# Main.net
KiCad netlist of a schematic drawn in EAGLE
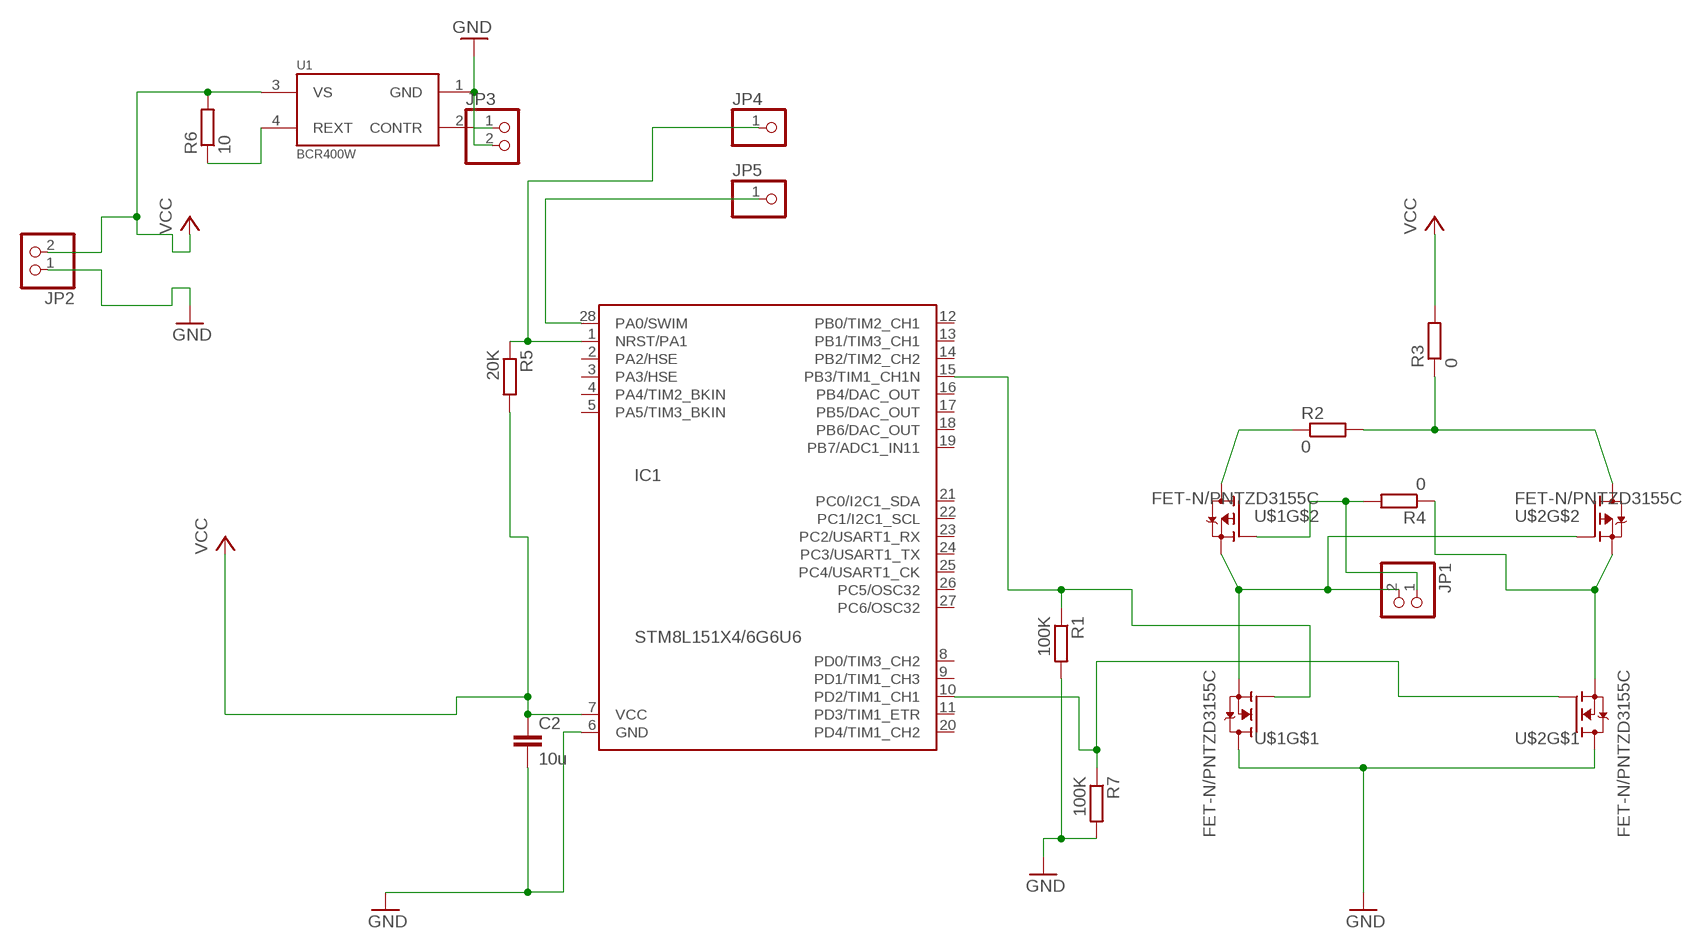
[diagram p0: schematic, sheet 1]

(export (version "E")
  (design (tool "Eeschema 10.0.6"))
  (components
    (comp (ref "C2")
      (value "10u")
      (footprint "eagle-import:C0805")
      (libsource (lib "eagle-import") (part "C-EUC0805"))
    )
    (comp (ref "IC1")
      (value "STM8L151X4/6G6U6")
      (footprint "eagle-import:QFN28")
      (libsource (lib "eagle-import") (part "STM8L151X4/6G6U6"))
    )
    (comp (ref "JP1")
      (value "PINHD-1X2")
      (footprint "eagle-import:1X02")
      (libsource (lib "eagle-import") (part "PINHD-1X2"))
    )
    (comp (ref "JP2")
      (value "PINHD-1X2")
      (footprint "eagle-import:1X02")
      (libsource (lib "eagle-import") (part "PINHD-1X2"))
    )
    (comp (ref "JP3")
      (value "PINHD-1X2")
      (footprint "eagle-import:1X02")
      (libsource (lib "eagle-import") (part "PINHD-1X2"))
    )
    (comp (ref "JP4")
      (value "PINHD-1X1")
      (footprint "eagle-import:1X01")
      (libsource (lib "eagle-import") (part "PINHD-1X1"))
    )
    (comp (ref "JP5")
      (value "PINHD-1X1")
      (footprint "eagle-import:1X01")
      (libsource (lib "eagle-import") (part "PINHD-1X1"))
    )
    (comp (ref "R1")
      (value "100K")
      (footprint "eagle-import:R0805")
      (libsource (lib "eagle-import") (part "R_0805"))
    )
    (comp (ref "R2")
      (value "0")
      (footprint "eagle-import:R0805")
      (libsource (lib "eagle-import") (part "R_0805"))
    )
    (comp (ref "R3")
      (value "0")
      (footprint "eagle-import:R0805")
      (libsource (lib "eagle-import") (part "R_0805"))
    )
    (comp (ref "R4")
      (value "0")
      (footprint "eagle-import:R0805")
      (libsource (lib "eagle-import") (part "R_0805"))
    )
    (comp (ref "R5")
      (value "20K")
      (footprint "eagle-import:R0805")
      (libsource (lib "eagle-import") (part "R_0805"))
    )
    (comp (ref "R6")
      (value "10")
      (footprint "eagle-import:R0805")
      (libsource (lib "eagle-import") (part "R_0805"))
    )
    (comp (ref "R7")
      (value "100K")
      (footprint "eagle-import:R0805")
      (libsource (lib "eagle-import") (part "R_0805"))
    )
    (comp (ref "U$1")
      (value "FET-N/PNTZD3155C")
      (footprint "eagle-import:SOT-563")
      (libsource (lib "eagle-import") (part "FET-N/PNTZD3155C"))
    )
    (comp (ref "U$2")
      (value "FET-N/PNTZD3155C")
      (footprint "eagle-import:SOT-563")
      (libsource (lib "eagle-import") (part "FET-N/PNTZD3155C"))
    )
    (comp (ref "U1")
      (value "BCR400W")
      (footprint "eagle-import:SOT130P210X100-4N")
      (libsource (lib "eagle-import") (part "BCR400W"))
    )
  )
  (nets
    (net (code "1") (name "GND") (class "Default")
      (node (ref "C2") (pin "2") (pinfunction "2_2") (pintype "passive"))
      (node (ref "IC1") (pin "6") (pinfunction "GND_6") (pintype "power_in"))
      (node (ref "JP2") (pin "1") (pinfunction "1_1") (pintype "passive"))
      (node (ref "JP3") (pin "2") (pinfunction "2_2") (pintype "passive"))
      (node (ref "R1") (pin "2") (pinfunction "2_2") (pintype "passive"))
      (node (ref "R7") (pin "2") (pinfunction "2_2") (pintype "passive"))
      (node (ref "U$1") (pin "6") (pinfunction "D_6") (pintype "passive"))
      (node (ref "U$2") (pin "6") (pinfunction "D_6") (pintype "passive"))
      (node (ref "U1") (pin "1") (pinfunction "GND_1") (pintype "power_in"))
    )
    (net (code "2") (name "Net-(IC1-NRST{slash}PA1)") (class "Default")
      (node (ref "IC1") (pin "1") (pinfunction "NRST/PA1_1") (pintype "bidirectional"))
      (node (ref "JP4") (pin "1") (pinfunction "1_1") (pintype "passive"))
      (node (ref "R5") (pin "1") (pinfunction "1_1") (pintype "passive"))
    )
    (net (code "3") (name "Net-(IC1-PA0{slash}SWIM)") (class "Default")
      (node (ref "IC1") (pin "28") (pinfunction "PA0/SWIM_28") (pintype "bidirectional"))
      (node (ref "JP5") (pin "1") (pinfunction "1_1") (pintype "passive"))
    )
    (net (code "4") (name "Net-(IC1-PB3{slash}TIM1_CH1N)") (class "Default")
      (node (ref "IC1") (pin "15") (pinfunction "PB3/TIM1_CH1N_15") (pintype "bidirectional"))
      (node (ref "R1") (pin "1") (pinfunction "1_1") (pintype "passive"))
      (node (ref "U$1") (pin "2") (pinfunction "G_2") (pintype "passive"))
    )
    (net (code "5") (name "Net-(IC1-PD2{slash}TIM1_CH1)") (class "Default")
      (node (ref "IC1") (pin "10") (pinfunction "PD2/TIM1_CH1_10") (pintype "bidirectional"))
      (node (ref "R7") (pin "1") (pinfunction "1_1") (pintype "passive"))
      (node (ref "U$2") (pin "2") (pinfunction "G_2") (pintype "passive"))
    )
    (net (code "6") (name "Net-(U$1A-S)") (class "Default")
      (node (ref "JP1") (pin "2") (pinfunction "2_2") (pintype "passive"))
      (node (ref "U$1") (pin "1") (pinfunction "S_1") (pintype "passive"))
      (node (ref "U$1") (pin "4") (pinfunction "S_4") (pintype "passive"))
      (node (ref "U$2") (pin "5") (pinfunction "G_5") (pintype "passive"))
    )
    (net (code "7") (name "Net-(U$1B-D)") (class "Default")
      (node (ref "R2") (pin "1") (pinfunction "1_1") (pintype "passive"))
      (node (ref "U$1") (pin "3") (pinfunction "D_3") (pintype "passive"))
    )
    (net (code "8") (name "Net-(U$1B-G)") (class "Default")
      (node (ref "JP1") (pin "1") (pinfunction "1_1") (pintype "passive"))
      (node (ref "R4") (pin "2") (pinfunction "2_2") (pintype "passive"))
      (node (ref "U$1") (pin "5") (pinfunction "G_5") (pintype "passive"))
    )
    (net (code "9") (name "Net-(U$2A-S)") (class "Default")
      (node (ref "R4") (pin "1") (pinfunction "1_1") (pintype "passive"))
      (node (ref "U$2") (pin "1") (pinfunction "S_1") (pintype "passive"))
      (node (ref "U$2") (pin "4") (pinfunction "S_4") (pintype "passive"))
    )
    (net (code "10") (name "Net-(U$2B-D)") (class "Default")
      (node (ref "R2") (pin "2") (pinfunction "2_2") (pintype "passive"))
      (node (ref "R3") (pin "1") (pinfunction "1_1") (pintype "passive"))
      (node (ref "U$2") (pin "3") (pinfunction "D_3") (pintype "passive"))
    )
    (net (code "11") (name "Net-(U1-CONTR)") (class "Default")
      (node (ref "JP3") (pin "1") (pinfunction "1_1") (pintype "passive"))
      (node (ref "U1") (pin "2") (pinfunction "CONTR_2") (pintype "passive"))
    )
    (net (code "12") (name "Net-(U1-REXT)") (class "Default")
      (node (ref "R6") (pin "1") (pinfunction "1_1") (pintype "passive"))
      (node (ref "U1") (pin "4") (pinfunction "REXT_4") (pintype "passive"))
    )
    (net (code "13") (name "VCC") (class "Default")
      (node (ref "C2") (pin "1") (pinfunction "1_1") (pintype "passive"))
      (node (ref "IC1") (pin "7") (pinfunction "VCC_7") (pintype "power_in"))
      (node (ref "JP2") (pin "2") (pinfunction "2_2") (pintype "passive"))
      (node (ref "R3") (pin "2") (pinfunction "2_2") (pintype "passive"))
      (node (ref "R5") (pin "2") (pinfunction "2_2") (pintype "passive"))
      (node (ref "R6") (pin "2") (pinfunction "2_2") (pintype "passive"))
      (node (ref "U1") (pin "3") (pinfunction "VS_3") (pintype "power_in"))
    )
    (net (code "14") (name "unconnected-(IC1-PA2{slash}HSE-Pad2)") (class "Default")
      (node (ref "IC1") (pin "2") (pinfunction "PA2/HSE_2") (pintype "bidirectional"))
    )
    (net (code "15") (name "unconnected-(IC1-PA3{slash}HSE-Pad3)") (class "Default")
      (node (ref "IC1") (pin "3") (pinfunction "PA3/HSE_3") (pintype "bidirectional"))
    )
    (net (code "16") (name "unconnected-(IC1-PA4{slash}TIM2_BKIN-Pad4)") (class "Default")
      (node (ref "IC1") (pin "4") (pinfunction "PA4/TIM2_BKIN_4") (pintype "bidirectional"))
    )
    (net (code "17") (name "unconnected-(IC1-PA5{slash}TIM3_BKIN-Pad5)") (class "Default")
      (node (ref "IC1") (pin "5") (pinfunction "PA5/TIM3_BKIN_5") (pintype "bidirectional"))
    )
    (net (code "18") (name "unconnected-(IC1-PB0{slash}TIM2_CH1-Pad12)") (class "Default")
      (node (ref "IC1") (pin "12") (pinfunction "PB0/TIM2_CH1_12") (pintype "bidirectional"))
    )
    (net (code "19") (name "unconnected-(IC1-PB1{slash}TIM3_CH1-Pad13)") (class "Default")
      (node (ref "IC1") (pin "13") (pinfunction "PB1/TIM3_CH1_13") (pintype "bidirectional"))
    )
    (net (code "20") (name "unconnected-(IC1-PB2{slash}TIM2_CH2-Pad14)") (class "Default")
      (node (ref "IC1") (pin "14") (pinfunction "PB2/TIM2_CH2_14") (pintype "bidirectional"))
    )
    (net (code "21") (name "unconnected-(IC1-PB4{slash}DAC_OUT-Pad16)") (class "Default")
      (node (ref "IC1") (pin "16") (pinfunction "PB4/DAC_OUT_16") (pintype "bidirectional"))
    )
    (net (code "22") (name "unconnected-(IC1-PB5{slash}DAC_OUT-Pad17)") (class "Default")
      (node (ref "IC1") (pin "17") (pinfunction "PB5/DAC_OUT_17") (pintype "bidirectional"))
    )
    (net (code "23") (name "unconnected-(IC1-PB6{slash}DAC_OUT-Pad18)") (class "Default")
      (node (ref "IC1") (pin "18") (pinfunction "PB6/DAC_OUT_18") (pintype "bidirectional"))
    )
    (net (code "24") (name "unconnected-(IC1-PB7{slash}ADC1_IN11-Pad19)") (class "Default")
      (node (ref "IC1") (pin "19") (pinfunction "PB7/ADC1_IN11_19") (pintype "bidirectional"))
    )
    (net (code "25") (name "unconnected-(IC1-PC0{slash}I2C1_SDA-Pad21)") (class "Default")
      (node (ref "IC1") (pin "21") (pinfunction "PC0/I2C1_SDA_21") (pintype "bidirectional"))
    )
    (net (code "26") (name "unconnected-(IC1-PC1{slash}I2C1_SCL-Pad22)") (class "Default")
      (node (ref "IC1") (pin "22") (pinfunction "PC1/I2C1_SCL_22") (pintype "bidirectional"))
    )
    (net (code "27") (name "unconnected-(IC1-PC2{slash}USART1_RX-Pad23)") (class "Default")
      (node (ref "IC1") (pin "23") (pinfunction "PC2/USART1_RX_23") (pintype "bidirectional"))
    )
    (net (code "28") (name "unconnected-(IC1-PC3{slash}USART1_TX-Pad24)") (class "Default")
      (node (ref "IC1") (pin "24") (pinfunction "PC3/USART1_TX_24") (pintype "bidirectional"))
    )
    (net (code "29") (name "unconnected-(IC1-PC4{slash}USART1_CK-Pad25)") (class "Default")
      (node (ref "IC1") (pin "25") (pinfunction "PC4/USART1_CK_25") (pintype "bidirectional"))
    )
    (net (code "30") (name "unconnected-(IC1-PC5{slash}OSC32-Pad26)") (class "Default")
      (node (ref "IC1") (pin "26") (pinfunction "PC5/OSC32_26") (pintype "bidirectional"))
    )
    (net (code "31") (name "unconnected-(IC1-PC6{slash}OSC32-Pad27)") (class "Default")
      (node (ref "IC1") (pin "27") (pinfunction "PC6/OSC32_27") (pintype "bidirectional"))
    )
    (net (code "32") (name "unconnected-(IC1-PD0{slash}TIM3_CH2-Pad8)") (class "Default")
      (node (ref "IC1") (pin "8") (pinfunction "PD0/TIM3_CH2_8") (pintype "bidirectional"))
    )
    (net (code "33") (name "unconnected-(IC1-PD1{slash}TIM1_CH3-Pad9)") (class "Default")
      (node (ref "IC1") (pin "9") (pinfunction "PD1/TIM1_CH3_9") (pintype "bidirectional"))
    )
    (net (code "34") (name "unconnected-(IC1-PD3{slash}TIM1_ETR-Pad11)") (class "Default")
      (node (ref "IC1") (pin "11") (pinfunction "PD3/TIM1_ETR_11") (pintype "bidirectional"))
    )
    (net (code "35") (name "unconnected-(IC1-PD4{slash}TIM1_CH2-Pad20)") (class "Default")
      (node (ref "IC1") (pin "20") (pinfunction "PD4/TIM1_CH2_20") (pintype "bidirectional"))
    )
  )
)
